# design.net
KiCad netlist of a schematic drawn in Altium Designer
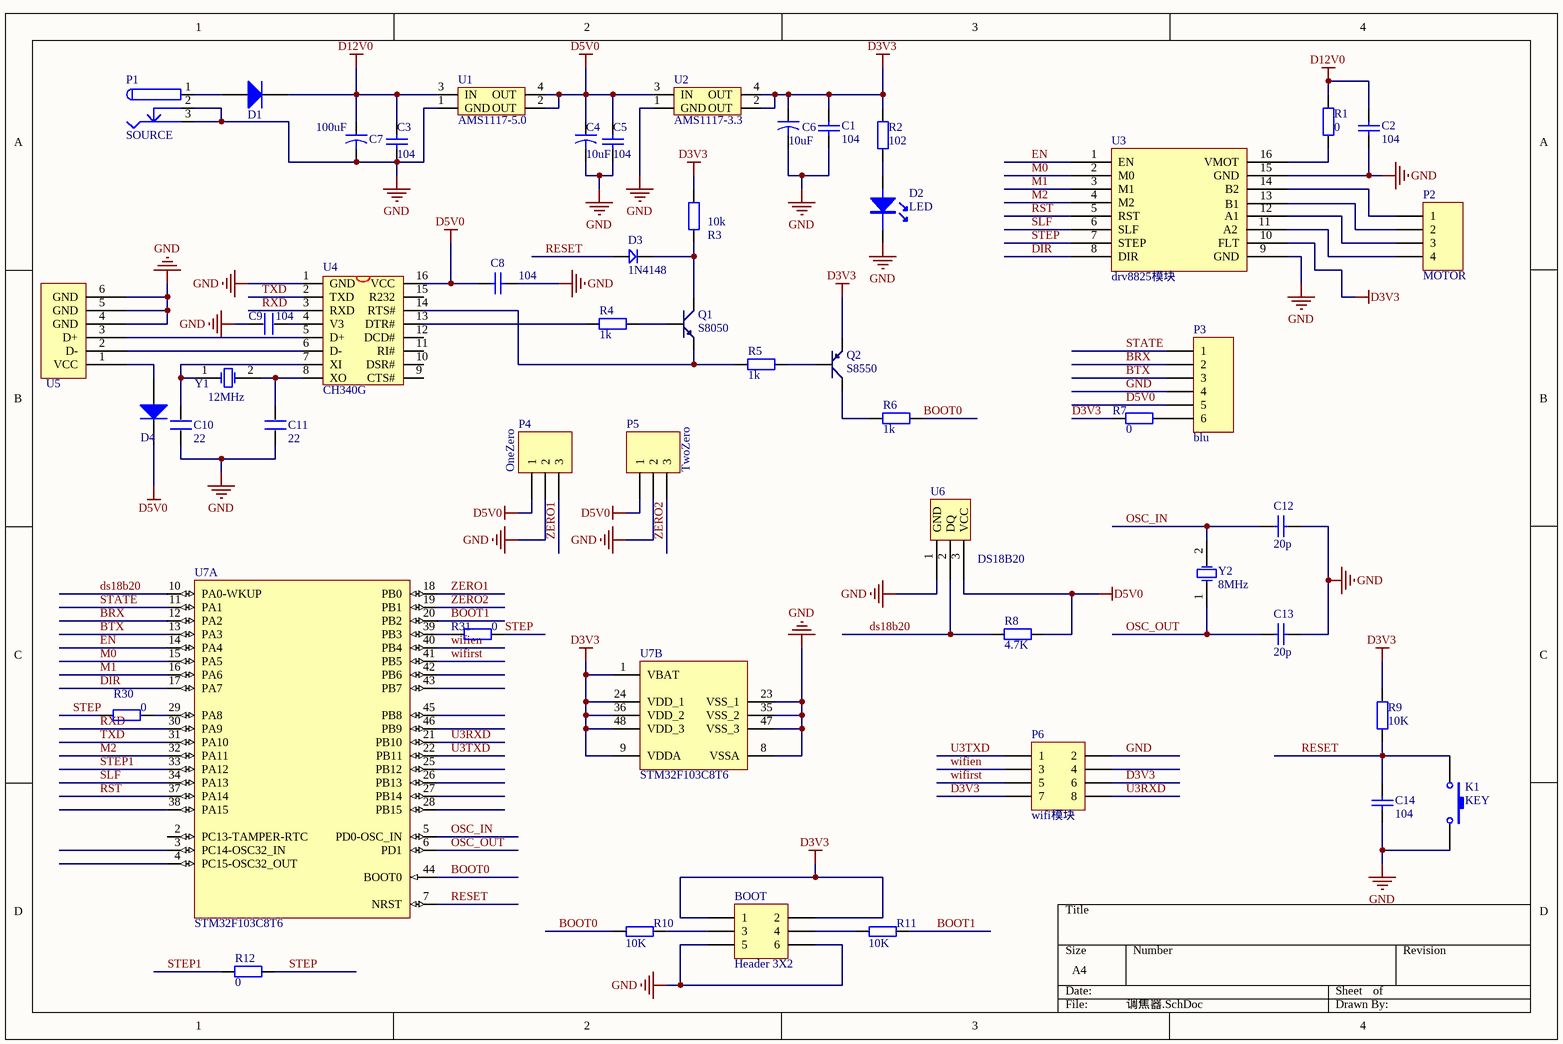
[diagram p0: 调焦器.SchDoc]

(export (version "E")
  (design (tool "Eeschema 10.0.6"))
  (components
    (comp (ref "BOOT")
      (value "Header 3X2")
      (footprint "HDR2X3")
      (description "Header, 3-Pin, Dual row")
      (fields (field (name "PUBLISHER") "Altium Limited"))
      (libsource (lib "WarShip V3 STM32103封装库") (part "Header 3X2"))
    )
    (comp (ref "C1")
      (value "104")
      (footprint "0805_cap")
      (description "Capacitor")
      (fields (field (name "Comment") "Cap") (field (name "PUBLISHER") "Altium Limited"))
      (libsource (lib "Crazy_PCB") (part "Cap"))
    )
    (comp (ref "C2")
      (value "104")
      (footprint "0805_cap")
      (description "Capacitor")
      (fields (field (name "Comment") "Cap") (field (name "PUBLISHER") "Altium Limited"))
      (libsource (lib "Crazy_PCB") (part "Cap"))
    )
    (comp (ref "C3")
      (value "104")
      (footprint "0805_cap")
      (description "Capacitor")
      (fields (field (name "Comment") "Cap") (field (name "PUBLISHER") "Altium Limited"))
      (libsource (lib "Crazy_PCB") (part "Cap"))
    )
    (comp (ref "C4")
      (value "CAP")
      (footprint "1812")
      (fields (field (name "VAULE") "10uF"))
      (libsource (lib "Crazy_PCB") (part "CAP2"))
    )
    (comp (ref "C5")
      (value "104")
      (footprint "0805_cap")
      (description "Capacitor")
      (fields (field (name "Comment") "Cap") (field (name "PUBLISHER") "Altium Limited"))
      (libsource (lib "Crazy_PCB") (part "Cap"))
    )
    (comp (ref "C6")
      (value "CAP")
      (footprint "1812")
      (fields (field (name "VAULE") "10uF"))
      (libsource (lib "Crazy_PCB") (part "CAP2"))
    )
    (comp (ref "C7")
      (value "CAP")
      (footprint "1000UF/16V")
      (fields (field (name "VAULE") "100uF"))
      (libsource (lib "Crazy_PCB") (part "CAP2"))
    )
    (comp (ref "C8")
      (value "104")
      (footprint "0805_cap")
      (description "Capacitor")
      (fields (field (name "Comment") "Cap") (field (name "PUBLISHER") "Altium Limited"))
      (libsource (lib "Crazy_PCB") (part "Cap"))
    )
    (comp (ref "C9") (value "104") (footprint "0805") (libsource (lib "WarShip V3 STM32103封装库") (part "C")))
    (comp (ref "C10") (value "22") (footprint "0805") (libsource (lib "WarShip V3 STM32103封装库") (part "C")))
    (comp (ref "C11") (value "22") (footprint "0805") (libsource (lib "WarShip V3 STM32103封装库") (part "C")))
    (comp (ref "C12")
      (value "20p")
      (footprint "0805_cap")
      (description "Capacitor")
      (fields (field (name "Comment") "Cap") (field (name "PUBLISHER") "Altium Limited"))
      (libsource (lib "Crazy_PCB") (part "Cap"))
    )
    (comp (ref "C13")
      (value "20p")
      (footprint "0805_cap")
      (description "Capacitor")
      (fields (field (name "Comment") "Cap") (field (name "PUBLISHER") "Altium Limited"))
      (libsource (lib "Crazy_PCB") (part "Cap"))
    )
    (comp (ref "C14")
      (value "104")
      (footprint "0805_cap")
      (description "Capacitor")
      (fields (field (name "Comment") "Cap") (field (name "PUBLISHER") "Altium Limited"))
      (libsource (lib "Crazy_PCB") (part "Cap"))
    )
    (comp (ref "D1")
      (value "Diode")
      (footprint "Diode")
      (description "High Conductance Fast Diode")
      (fields (field (name "PUBLISHER") "Altium Limited"))
      (libsource (lib "Crazy_PCB") (part "Diode"))
    )
    (comp (ref "D2")
      (value "LED")
      (footprint "LED")
      (description "LED 发光二极管")
      (libsource (lib "Crazy_PCB") (part "LED"))
    )
    (comp (ref "D3") (value "1N4148") (footprint "Diode") (libsource (lib "MiniSTM32 V3.0封装库") (part "D")))
    (comp (ref "D4")
      (value "Diode")
      (footprint "Diode")
      (description "High Conductance Fast Diode")
      (fields (field (name "PUBLISHER") "Altium Limited"))
      (libsource (lib "Crazy_PCB") (part "Diode"))
    )
    (comp (ref "K1")
      (value "KEY")
      (footprint "KEY2")
      (description "Switch")
      (fields (field (name "PUBLISHER") "Altium Limited"))
      (libsource (lib "Crazy_PCB") (part "KEY2"))
    )
    (comp (ref "P1")
      (value "SOURCE")
      (footprint "source")
      (fields (field (name "PUBLISHER") "Altium Limited"))
      (libsource (lib "Crazy_PCB") (part "SOURCE"))
    )
    (comp (ref "P2")
      (value "MOTOR")
      (footprint "HDR1X4")
      (description "Header, 4-Pin")
      (fields (field (name "PUBLISHER") "Altium Limited"))
      (libsource (lib "Miscellaneous Connectors") (part "Header 4"))
    )
    (comp (ref "P3")
      (value "blu")
      (footprint "HDR1X6")
      (description "Header, 6-Pin")
      (fields (field (name "PUBLISHER") "Altium Limited"))
      (libsource (lib "Miscellaneous Connectors") (part "Header 6"))
    )
    (comp (ref "P4")
      (value "OneZero")
      (footprint "HDR1X3")
      (description "Header, 3-Pin")
      (fields (field (name "PUBLISHER") "Altium Limited"))
      (libsource (lib "Miscellaneous Connectors") (part "Header 3"))
    )
    (comp (ref "P5")
      (value "TwoZero")
      (footprint "HDR1X3")
      (description "Header, 3-Pin")
      (fields (field (name "PUBLISHER") "Altium Limited"))
      (libsource (lib "Miscellaneous Connectors") (part "Header 3"))
    )
    (comp (ref "P6")
      (value "wifi模块")
      (footprint "HDR2X4")
      (description "Header, 4-Pin, Dual row")
      (fields (field (name "PUBLISHER") "Altium Limited"))
      (libsource (lib "Miscellaneous Connectors") (part "Header 4X2"))
    )
    (comp (ref "Q1")
      (value "S8050")
      (footprint "SOT-23R")
      (description "8050/BCW846/BCW847")
      (libsource (lib "MiniSTM32 V3.0封装库") (part "NPN"))
    )
    (comp (ref "Q2")
      (value "S8550")
      (footprint "SOT-23R")
      (description "8550/BCW68")
      (libsource (lib "MiniSTM32 V3.0封装库") (part "PNP"))
    )
    (comp (ref "R1")
      (value "0")
      (footprint "0805")
      (description "Resistor")
      (fields (field (name "PUBLISHER") "Altium Limited"))
      (libsource (lib "") (part "RES_1"))
    )
    (comp (ref "R2")
      (value "102")
      (footprint "0805")
      (description "Resistor")
      (fields (field (name "PUBLISHER") "Altium Limited"))
      (libsource (lib "") (part "RES_1"))
    )
    (comp (ref "R3")
      (value "10k")
      (footprint "0805")
      (description "Resistor")
      (fields (field (name "PUBLISHER") "Altium Limited"))
      (libsource (lib "") (part "RES_1"))
    )
    (comp (ref "R4")
      (value "1k")
      (footprint "0805")
      (description "Resistor")
      (fields (field (name "PUBLISHER") "Altium Limited"))
      (libsource (lib "Crazy_PCB") (part "RES"))
    )
    (comp (ref "R5")
      (value "1k")
      (footprint "0805")
      (description "Resistor")
      (fields (field (name "PUBLISHER") "Altium Limited"))
      (libsource (lib "Crazy_PCB") (part "RES"))
    )
    (comp (ref "R6")
      (value "1k")
      (footprint "0805")
      (description "Resistor")
      (fields (field (name "PUBLISHER") "Altium Limited"))
      (libsource (lib "Crazy_PCB") (part "RES"))
    )
    (comp (ref "R7")
      (value "0")
      (footprint "0805")
      (description "Resistor")
      (fields (field (name "PUBLISHER") "Altium Limited"))
      (libsource (lib "Crazy_PCB") (part "RES"))
    )
    (comp (ref "R8")
      (value "4.7K")
      (footprint "0805")
      (description "Resistor")
      (fields (field (name "PUBLISHER") "Altium Limited"))
      (libsource (lib "Crazy_PCB") (part "RES"))
    )
    (comp (ref "R9")
      (value "10K")
      (footprint "0805")
      (description "Resistor")
      (fields (field (name "PUBLISHER") "Altium Limited"))
      (libsource (lib "") (part "RES_1"))
    )
    (comp (ref "R10") (value "10K") (footprint "0805") (libsource (lib "WarShip V3 STM32103封装库") (part "R")))
    (comp (ref "R11") (value "10K") (footprint "0805") (libsource (lib "WarShip V3 STM32103封装库") (part "R")))
    (comp (ref "R12")
      (value "0")
      (footprint "0805")
      (description "Resistor")
      (fields (field (name "PUBLISHER") "Altium Limited"))
      (libsource (lib "Crazy_PCB") (part "RES"))
    )
    (comp (ref "R30")
      (value "0")
      (footprint "0805")
      (description "Resistor")
      (fields (field (name "PUBLISHER") "Altium Limited"))
      (libsource (lib "Crazy_PCB") (part "RES"))
    )
    (comp (ref "R31")
      (value "0")
      (footprint "0805")
      (description "Resistor")
      (fields (field (name "PUBLISHER") "Altium Limited"))
      (libsource (lib "Crazy_PCB") (part "RES"))
    )
    (comp (ref "U1")
      (value "AMS1117-5.0")
      (footprint "AMS1117")
      (libsource (lib "MiniSTM32 V3.0封装库") (part "AMS1117"))
    )
    (comp (ref "U2")
      (value "AMS1117-3.3")
      (footprint "AMS1117")
      (libsource (lib "MiniSTM32 V3.0封装库") (part "AMS1117"))
    )
    (comp (ref "U3")
      (value "drv8825模块")
      (footprint "DRV8825模块 - duplicate")
      (libsource (lib "DX") (part "drv8825模块"))
    )
    (comp (ref "U4")
      (value "CH340G")
      (footprint "SOP16M")
      (description "USB2UART")
      (libsource (lib "WarShip V3 STM32103封装库") (part "CH340G"))
    )
    (comp (ref "U5") (value "USB-B") (footprint "USB_B") (libsource (lib "DX") (part "USB-B")))
    (comp (ref "U6")
      (value "DS18B20")
      (footprint "DS18B20")
      (libsource (lib "MiniSTM32 V3.0封装库") (part "DS18B20"))
    )
    (comp (ref "U7")
      (value "STM32F103C8T6")
      (footprint "LQFP48_N")
      (libsource (lib "STMicroelectronics STM32 F1") (part "STM32F103C8T6"))
    )
    (comp (ref "Y1")
      (value "12MHz")
      (footprint "XTAL_US")
      (description "Crystal Oscillator")
      (fields (field (name "PUBLISHER") "Altium Limited"))
      (libsource (lib "WarShip V3 STM32103封装库") (part "XTAL"))
    )
    (comp (ref "Y2")
      (value "8MHz")
      (footprint "XTAL_US")
      (description "Crystal Oscillator")
      (fields (field (name "PUBLISHER") "Altium Limited"))
      (libsource (lib "MiniSTM32 V3.0封装库") (part "XTAL"))
    )
  )
  (nets
    (net (code "1") (name "/BOOT0") (class "Default")
      (node (ref "R10") (pin "1") (pintype "passive"))
      (node (ref "R6") (pin "2") (pinfunction "2_2") (pintype "passive"))
      (node (ref "U7") (pin "44") (pinfunction "BOOT0_44") (pintype "input"))
    )
    (net (code "2") (name "/BOOT1") (class "Default")
      (node (ref "R11") (pin "2") (pintype "passive"))
      (node (ref "U7") (pin "20") (pinfunction "PB2_20") (pintype "bidirectional"))
    )
    (net (code "3") (name "/BRX") (class "Default")
      (node (ref "P3") (pin "2") (pinfunction "2_2") (pintype "passive"))
      (node (ref "U7") (pin "12") (pinfunction "PA2_12") (pintype "bidirectional"))
    )
    (net (code "4") (name "/BTX") (class "Default")
      (node (ref "P3") (pin "3") (pinfunction "3_3") (pintype "passive"))
      (node (ref "U7") (pin "13") (pinfunction "PA3_13") (pintype "bidirectional"))
    )
    (net (code "5") (name "/DIR") (class "Default")
      (node (ref "U3") (pin "8") (pinfunction "DIR_8") (pintype "passive"))
      (node (ref "U7") (pin "17") (pinfunction "PA7_17") (pintype "bidirectional"))
    )
    (net (code "6") (name "/EN") (class "Default")
      (node (ref "U3") (pin "1") (pinfunction "EN_1") (pintype "passive"))
      (node (ref "U7") (pin "14") (pinfunction "PA4_14") (pintype "bidirectional"))
    )
    (net (code "7") (name "/M0") (class "Default")
      (node (ref "U3") (pin "2") (pinfunction "M0_2") (pintype "passive"))
      (node (ref "U7") (pin "15") (pinfunction "PA5_15") (pintype "bidirectional"))
    )
    (net (code "8") (name "/M1") (class "Default")
      (node (ref "U3") (pin "3") (pinfunction "M1_3") (pintype "passive"))
      (node (ref "U7") (pin "16") (pinfunction "PA6_16") (pintype "bidirectional"))
    )
    (net (code "9") (name "/M2") (class "Default")
      (node (ref "U3") (pin "4") (pinfunction "M2_4") (pintype "passive"))
      (node (ref "U7") (pin "32") (pinfunction "PA11_32") (pintype "bidirectional"))
    )
    (net (code "10") (name "/OSC_IN") (class "Default")
      (node (ref "C12") (pin "1") (pinfunction "1_1") (pintype "passive"))
      (node (ref "U7") (pin "5") (pinfunction "PD0-OSC_IN_5") (pintype "bidirectional"))
      (node (ref "Y2") (pin "2") (pinfunction "OSC2_2") (pintype "passive"))
    )
    (net (code "11") (name "/OSC_OUT") (class "Default")
      (node (ref "C13") (pin "1") (pinfunction "1_1") (pintype "passive"))
      (node (ref "U7") (pin "6") (pinfunction "PD1_6") (pintype "bidirectional"))
      (node (ref "Y2") (pin "1") (pinfunction "OSC1_1") (pintype "passive"))
    )
    (net (code "12") (name "/RESET") (class "Default")
      (node (ref "C14") (pin "2") (pinfunction "2_2") (pintype "passive"))
      (node (ref "D3") (pin "1") (pintype "passive"))
      (node (ref "K1") (pin "1") (pinfunction "1_1") (pintype "passive"))
      (node (ref "R9") (pin "1") (pinfunction "1_1") (pintype "passive"))
      (node (ref "U7") (pin "7") (pinfunction "NRST_7") (pintype "bidirectional"))
    )
    (net (code "13") (name "/RST") (class "Default")
      (node (ref "U3") (pin "5") (pinfunction "RST_5") (pintype "passive"))
      (node (ref "U7") (pin "37") (pinfunction "PA14_37") (pintype "bidirectional"))
    )
    (net (code "14") (name "/RXD") (class "Default")
      (node (ref "U4") (pin "3") (pinfunction "RXD_3") (pintype "passive"))
      (node (ref "U7") (pin "30") (pinfunction "PA9_30") (pintype "bidirectional"))
    )
    (net (code "15") (name "/SLF") (class "Default")
      (node (ref "U3") (pin "6") (pinfunction "SLF_6") (pintype "passive"))
      (node (ref "U7") (pin "34") (pinfunction "PA13_34") (pintype "bidirectional"))
    )
    (net (code "16") (name "/STATE") (class "Default")
      (node (ref "P3") (pin "1") (pinfunction "1_1") (pintype "passive"))
      (node (ref "U7") (pin "11") (pinfunction "PA1_11") (pintype "bidirectional"))
    )
    (net (code "17") (name "/STEP") (class "Default")
      (node (ref "R12") (pin "2") (pinfunction "2_2") (pintype "passive"))
      (node (ref "R30") (pin "1") (pinfunction "1_1") (pintype "passive"))
      (node (ref "R31") (pin "2") (pinfunction "2_2") (pintype "passive"))
      (node (ref "U3") (pin "7") (pinfunction "STEP_7") (pintype "passive"))
    )
    (net (code "18") (name "/STEP1") (class "Default")
      (node (ref "R12") (pin "1") (pinfunction "1_1") (pintype "passive"))
      (node (ref "U7") (pin "33") (pinfunction "PA12_33") (pintype "bidirectional"))
    )
    (net (code "19") (name "/TXD") (class "Default")
      (node (ref "U4") (pin "2") (pinfunction "TXD_2") (pintype "passive"))
      (node (ref "U7") (pin "31") (pinfunction "PA10_31") (pintype "bidirectional"))
    )
    (net (code "20") (name "/U3RXD") (class "Default")
      (node (ref "P6") (pin "8") (pinfunction "8_8") (pintype "passive"))
      (node (ref "U7") (pin "21") (pinfunction "PB10_21") (pintype "bidirectional"))
    )
    (net (code "21") (name "/U3TXD") (class "Default")
      (node (ref "P6") (pin "1") (pinfunction "1_1") (pintype "passive"))
      (node (ref "U7") (pin "22") (pinfunction "PB11_22") (pintype "bidirectional"))
    )
    (net (code "22") (name "/ZERO1") (class "Default")
      (node (ref "P4") (pin "3") (pinfunction "3_3") (pintype "passive"))
      (node (ref "U7") (pin "18") (pinfunction "PB0_18") (pintype "bidirectional"))
    )
    (net (code "23") (name "/ZERO2") (class "Default")
      (node (ref "P5") (pin "3") (pinfunction "3_3") (pintype "passive"))
      (node (ref "U7") (pin "19") (pinfunction "PB1_19") (pintype "bidirectional"))
    )
    (net (code "24") (name "/ds18b20") (class "Default")
      (node (ref "R8") (pin "1") (pinfunction "1_1") (pintype "passive"))
      (node (ref "U6") (pin "2") (pinfunction "DQ_2") (pintype "passive"))
      (node (ref "U7") (pin "10") (pinfunction "PA0-WKUP_10") (pintype "bidirectional"))
    )
    (net (code "25") (name "/wifien") (class "Default")
      (node (ref "P6") (pin "3") (pinfunction "3_3") (pintype "passive"))
      (node (ref "U7") (pin "40") (pinfunction "PB4_40") (pintype "bidirectional"))
    )
    (net (code "26") (name "/wifirst") (class "Default")
      (node (ref "P6") (pin "5") (pinfunction "5_5") (pintype "passive"))
      (node (ref "U7") (pin "41") (pinfunction "PB5_41") (pintype "bidirectional"))
    )
    (net (code "27") (name "D3V3") (class "Default")
      (node (ref "BOOT") (pin "1") (pinfunction "1_1") (pintype "passive"))
      (node (ref "BOOT") (pin "2") (pinfunction "2_2") (pintype "passive"))
      (node (ref "C1") (pin "2") (pinfunction "2_2") (pintype "passive"))
      (node (ref "C6") (pin "1") (pinfunction "1_1") (pintype "passive"))
      (node (ref "P6") (pin "6") (pinfunction "6_6") (pintype "passive"))
      (node (ref "P6") (pin "7") (pinfunction "7_7") (pintype "passive"))
      (node (ref "Q2") (pin "1") (pinfunction "E_1") (pintype "passive"))
      (node (ref "R2") (pin "2") (pinfunction "2_2") (pintype "passive"))
      (node (ref "R3") (pin "2") (pinfunction "2_2") (pintype "passive"))
      (node (ref "R7") (pin "1") (pinfunction "1_1") (pintype "passive"))
      (node (ref "R9") (pin "2") (pinfunction "2_2") (pintype "passive"))
      (node (ref "U2") (pin "2") (pinfunction "OUT_2") (pintype "passive"))
      (node (ref "U2") (pin "4") (pinfunction "OUT_4") (pintype "passive"))
      (node (ref "U3") (pin "10") (pinfunction "FLT_10") (pintype "passive"))
      (node (ref "U7") (pin "1") (pinfunction "VBAT_1") (pintype "power_in"))
      (node (ref "U7") (pin "24") (pinfunction "VDD_1_24") (pintype "power_in"))
      (node (ref "U7") (pin "36") (pinfunction "VDD_2_36") (pintype "power_in"))
      (node (ref "U7") (pin "48") (pinfunction "VDD_3_48") (pintype "power_in"))
      (node (ref "U7") (pin "9") (pinfunction "VDDA_9") (pintype "power_in"))
    )
    (net (code "28") (name "D5V0") (class "Default")
      (node (ref "C4") (pin "1") (pinfunction "1_1") (pintype "passive"))
      (node (ref "C5") (pin "2") (pinfunction "2_2") (pintype "passive"))
      (node (ref "C8") (pin "2") (pinfunction "2_2") (pintype "passive"))
      (node (ref "D4") (pin "2") (pinfunction "K_2") (pintype "passive"))
      (node (ref "P3") (pin "5") (pinfunction "5_5") (pintype "passive"))
      (node (ref "P4") (pin "1") (pinfunction "1_1") (pintype "passive"))
      (node (ref "P5") (pin "1") (pinfunction "1_1") (pintype "passive"))
      (node (ref "R8") (pin "2") (pinfunction "2_2") (pintype "passive"))
      (node (ref "U1") (pin "2") (pinfunction "OUT_2") (pintype "passive"))
      (node (ref "U1") (pin "4") (pinfunction "OUT_4") (pintype "passive"))
      (node (ref "U2") (pin "3") (pinfunction "IN_3") (pintype "passive"))
      (node (ref "U4") (pin "16") (pinfunction "VCC_16") (pintype "passive"))
      (node (ref "U6") (pin "3") (pinfunction "VCC_3") (pintype "passive"))
    )
    (net (code "29") (name "D12V0") (class "Default")
      (node (ref "C2") (pin "2") (pinfunction "2_2") (pintype "passive"))
      (node (ref "C3") (pin "2") (pinfunction "2_2") (pintype "passive"))
      (node (ref "C7") (pin "1") (pinfunction "1_1") (pintype "passive"))
      (node (ref "D1") (pin "2") (pinfunction "K_2") (pintype "passive"))
      (node (ref "R1") (pin "2") (pinfunction "2_2") (pintype "passive"))
      (node (ref "U1") (pin "3") (pinfunction "IN_3") (pintype "passive"))
    )
    (net (code "30") (name "GND") (class "Default")
      (node (ref "BOOT") (pin "5") (pinfunction "5_5") (pintype "passive"))
      (node (ref "BOOT") (pin "6") (pinfunction "6_6") (pintype "passive"))
      (node (ref "C1") (pin "1") (pinfunction "1_1") (pintype "passive"))
      (node (ref "C10") (pin "1") (pintype "passive"))
      (node (ref "C11") (pin "1") (pintype "passive"))
      (node (ref "C12") (pin "2") (pinfunction "2_2") (pintype "passive"))
      (node (ref "C13") (pin "2") (pinfunction "2_2") (pintype "passive"))
      (node (ref "C14") (pin "1") (pinfunction "1_1") (pintype "passive"))
      (node (ref "C2") (pin "1") (pinfunction "1_1") (pintype "passive"))
      (node (ref "C3") (pin "1") (pinfunction "1_1") (pintype "passive"))
      (node (ref "C4") (pin "2") (pinfunction "2_2") (pintype "passive"))
      (node (ref "C5") (pin "1") (pinfunction "1_1") (pintype "passive"))
      (node (ref "C6") (pin "2") (pinfunction "2_2") (pintype "passive"))
      (node (ref "C7") (pin "2") (pinfunction "2_2") (pintype "passive"))
      (node (ref "C8") (pin "1") (pinfunction "1_1") (pintype "passive"))
      (node (ref "C9") (pin "1") (pintype "passive"))
      (node (ref "D2") (pin "2") (pinfunction "K_2") (pintype "passive"))
      (node (ref "K1") (pin "2") (pinfunction "2_2") (pintype "passive"))
      (node (ref "P1") (pin "2") (pinfunction "2_2") (pintype "power_in"))
      (node (ref "P1") (pin "3") (pinfunction "3_3") (pintype "power_in"))
      (node (ref "P3") (pin "4") (pinfunction "4_4") (pintype "passive"))
      (node (ref "P4") (pin "2") (pinfunction "2_2") (pintype "passive"))
      (node (ref "P5") (pin "2") (pinfunction "2_2") (pintype "passive"))
      (node (ref "P6") (pin "2") (pinfunction "2_2") (pintype "passive"))
      (node (ref "U1") (pin "1") (pinfunction "GND_1") (pintype "passive"))
      (node (ref "U2") (pin "1") (pinfunction "GND_1") (pintype "passive"))
      (node (ref "U3") (pin "15") (pinfunction "GND_15") (pintype "passive"))
      (node (ref "U3") (pin "9") (pinfunction "GND_9") (pintype "passive"))
      (node (ref "U4") (pin "1") (pinfunction "GND_1") (pintype "passive"))
      (node (ref "U5") (pin "4") (pinfunction "GND_4") (pintype "passive"))
      (node (ref "U5") (pin "5") (pinfunction "GND_5") (pintype "passive"))
      (node (ref "U5") (pin "6") (pinfunction "GND_6") (pintype "passive"))
      (node (ref "U6") (pin "1") (pinfunction "GND_1") (pintype "passive"))
      (node (ref "U7") (pin "23") (pinfunction "VSS_1_23") (pintype "power_in"))
      (node (ref "U7") (pin "35") (pinfunction "VSS_2_35") (pintype "power_in"))
      (node (ref "U7") (pin "47") (pinfunction "VSS_3_47") (pintype "power_in"))
      (node (ref "U7") (pin "8") (pinfunction "VSSA_8") (pintype "power_in"))
    )
    (net (code "31") (name "Net-(BOOT-Pad3)") (class "Default")
      (node (ref "BOOT") (pin "3") (pinfunction "3_3") (pintype "passive"))
      (node (ref "R10") (pin "2") (pintype "passive"))
    )
    (net (code "32") (name "Net-(BOOT-Pad4)") (class "Default")
      (node (ref "BOOT") (pin "4") (pinfunction "4_4") (pintype "passive"))
      (node (ref "R11") (pin "1") (pintype "passive"))
    )
    (net (code "33") (name "Net-(D1-A)") (class "Default")
      (node (ref "D1") (pin "1") (pinfunction "A_1") (pintype "passive"))
      (node (ref "P1") (pin "1") (pinfunction "1_1") (pintype "power_in"))
    )
    (net (code "34") (name "Net-(D2-A)") (class "Default")
      (node (ref "D2") (pin "1") (pinfunction "A_1") (pintype "passive"))
      (node (ref "R2") (pin "1") (pinfunction "1_1") (pintype "passive"))
    )
    (net (code "35") (name "Net-(D4-A)") (class "Default")
      (node (ref "D4") (pin "1") (pinfunction "A_1") (pintype "passive"))
      (node (ref "U5") (pin "1") (pinfunction "VCC_1") (pintype "passive"))
    )
    (net (code "36") (name "Net-(P3-Pad6)") (class "Default")
      (node (ref "P3") (pin "6") (pinfunction "6_6") (pintype "passive"))
      (node (ref "R7") (pin "2") (pinfunction "2_2") (pintype "passive"))
    )
    (net (code "37") (name "Net-(Q1-B)") (class "Default")
      (node (ref "Q1") (pin "2") (pinfunction "B_2") (pintype "passive"))
      (node (ref "R4") (pin "2") (pinfunction "2_2") (pintype "passive"))
    )
    (net (code "38") (name "Net-(Q1-C)") (class "Default")
      (node (ref "D3") (pin "2") (pintype "passive"))
      (node (ref "Q1") (pin "3") (pinfunction "C_3") (pintype "passive"))
      (node (ref "R3") (pin "1") (pinfunction "1_1") (pintype "passive"))
    )
    (net (code "39") (name "Net-(Q1-E)") (class "Default")
      (node (ref "Q1") (pin "1") (pinfunction "E_1") (pintype "passive"))
      (node (ref "R5") (pin "1") (pinfunction "1_1") (pintype "passive"))
      (node (ref "U4") (pin "14") (pinfunction "RTS#_14") (pintype "passive"))
    )
    (net (code "40") (name "Net-(Q2-B)") (class "Default")
      (node (ref "Q2") (pin "2") (pinfunction "B_2") (pintype "passive"))
      (node (ref "R5") (pin "2") (pinfunction "2_2") (pintype "passive"))
    )
    (net (code "41") (name "Net-(Q2-C)") (class "Default")
      (node (ref "Q2") (pin "3") (pinfunction "C_3") (pintype "passive"))
      (node (ref "R6") (pin "1") (pinfunction "1_1") (pintype "passive"))
    )
    (net (code "42") (name "Net-(U3-A1)") (class "Default")
      (node (ref "P2") (pin "3") (pinfunction "3_3") (pintype "passive"))
      (node (ref "U3") (pin "12") (pinfunction "A1_12") (pintype "passive"))
    )
    (net (code "43") (name "Net-(U3-A2)") (class "Default")
      (node (ref "P2") (pin "4") (pinfunction "4_4") (pintype "passive"))
      (node (ref "U3") (pin "11") (pinfunction "A2_11") (pintype "passive"))
    )
    (net (code "44") (name "Net-(U3-B1)") (class "Default")
      (node (ref "P2") (pin "2") (pinfunction "2_2") (pintype "passive"))
      (node (ref "U3") (pin "13") (pinfunction "B1_13") (pintype "passive"))
    )
    (net (code "45") (name "Net-(U3-B2)") (class "Default")
      (node (ref "P2") (pin "1") (pinfunction "1_1") (pintype "passive"))
      (node (ref "U3") (pin "14") (pinfunction "B2_14") (pintype "passive"))
    )
    (net (code "46") (name "Net-(U3-VMOT)") (class "Default")
      (node (ref "R1") (pin "1") (pinfunction "1_1") (pintype "passive"))
      (node (ref "U3") (pin "16") (pinfunction "VMOT_16") (pintype "passive"))
    )
    (net (code "47") (name "Net-(U4-D+)") (class "Default")
      (node (ref "U4") (pin "5") (pinfunction "D+_5") (pintype "passive"))
      (node (ref "U5") (pin "3") (pinfunction "D+_3") (pintype "passive"))
    )
    (net (code "48") (name "Net-(U4-D-)") (class "Default")
      (node (ref "U4") (pin "6") (pinfunction "D-_6") (pintype "passive"))
      (node (ref "U5") (pin "2") (pinfunction "D-_2") (pintype "passive"))
    )
    (net (code "49") (name "Net-(U4-DTR#)") (class "Default")
      (node (ref "R4") (pin "1") (pinfunction "1_1") (pintype "passive"))
      (node (ref "U4") (pin "13") (pinfunction "DTR#_13") (pintype "passive"))
    )
    (net (code "50") (name "Net-(U4-V3)") (class "Default")
      (node (ref "C9") (pin "2") (pintype "passive"))
      (node (ref "U4") (pin "4") (pinfunction "V3_4") (pintype "passive"))
    )
    (net (code "51") (name "Net-(U4-XI)") (class "Default")
      (node (ref "C10") (pin "2") (pintype "passive"))
      (node (ref "U4") (pin "7") (pinfunction "XI_7") (pintype "passive"))
      (node (ref "Y1") (pin "1") (pinfunction "OSC1_1") (pintype "passive"))
    )
    (net (code "52") (name "Net-(U4-XO)") (class "Default")
      (node (ref "C11") (pin "2") (pintype "passive"))
      (node (ref "U4") (pin "8") (pinfunction "XO_8") (pintype "passive"))
      (node (ref "Y1") (pin "2") (pinfunction "OSC2_2") (pintype "passive"))
    )
    (net (code "53") (name "Net-(U7A-PA8)") (class "Default")
      (node (ref "R30") (pin "2") (pinfunction "2_2") (pintype "passive"))
      (node (ref "U7") (pin "29") (pinfunction "PA8_29") (pintype "bidirectional"))
    )
    (net (code "54") (name "Net-(U7A-PB3)") (class "Default")
      (node (ref "R31") (pin "1") (pinfunction "1_1") (pintype "passive"))
      (node (ref "U7") (pin "39") (pinfunction "PB3_39") (pintype "bidirectional"))
    )
    (net (code "55") (name "unconnected-(P6-Pad4)") (class "Default")
      (node (ref "P6") (pin "4") (pinfunction "4_4") (pintype "passive"))
    )
    (net (code "56") (name "unconnected-(U4-CTS#-Pad9)") (class "Default")
      (node (ref "U4") (pin "9") (pinfunction "CTS#_9") (pintype "passive"))
    )
    (net (code "57") (name "unconnected-(U4-DCD#-Pad12)") (class "Default")
      (node (ref "U4") (pin "12") (pinfunction "DCD#_12") (pintype "passive"))
    )
    (net (code "58") (name "unconnected-(U4-DSR#-Pad10)") (class "Default")
      (node (ref "U4") (pin "10") (pinfunction "DSR#_10") (pintype "passive"))
    )
    (net (code "59") (name "unconnected-(U4-R232-Pad15)") (class "Default")
      (node (ref "U4") (pin "15") (pinfunction "R232_15") (pintype "passive"))
    )
    (net (code "60") (name "unconnected-(U4-RI#-Pad11)") (class "Default")
      (node (ref "U4") (pin "11") (pinfunction "RI#_11") (pintype "passive"))
    )
    (net (code "61") (name "unconnected-(U7A-PA15-Pad38)") (class "Default")
      (node (ref "U7") (pin "38") (pinfunction "PA15_38") (pintype "bidirectional"))
    )
    (net (code "62") (name "unconnected-(U7A-PB6-Pad42)") (class "Default")
      (node (ref "U7") (pin "42") (pinfunction "PB6_42") (pintype "bidirectional"))
    )
    (net (code "63") (name "unconnected-(U7A-PB7-Pad43)") (class "Default")
      (node (ref "U7") (pin "43") (pinfunction "PB7_43") (pintype "bidirectional"))
    )
    (net (code "64") (name "unconnected-(U7A-PB8-Pad45)") (class "Default")
      (node (ref "U7") (pin "45") (pinfunction "PB8_45") (pintype "bidirectional"))
    )
    (net (code "65") (name "unconnected-(U7A-PB9-Pad46)") (class "Default")
      (node (ref "U7") (pin "46") (pinfunction "PB9_46") (pintype "bidirectional"))
    )
    (net (code "66") (name "unconnected-(U7A-PB12-Pad25)") (class "Default")
      (node (ref "U7") (pin "25") (pinfunction "PB12_25") (pintype "bidirectional"))
    )
    (net (code "67") (name "unconnected-(U7A-PB13-Pad26)") (class "Default")
      (node (ref "U7") (pin "26") (pinfunction "PB13_26") (pintype "bidirectional"))
    )
    (net (code "68") (name "unconnected-(U7A-PB14-Pad27)") (class "Default")
      (node (ref "U7") (pin "27") (pinfunction "PB14_27") (pintype "bidirectional"))
    )
    (net (code "69") (name "unconnected-(U7A-PB15-Pad28)") (class "Default")
      (node (ref "U7") (pin "28") (pinfunction "PB15_28") (pintype "bidirectional"))
    )
    (net (code "70") (name "unconnected-(U7A-PC13-TAMPER-RTC-Pad2)") (class "Default")
      (node (ref "U7") (pin "2") (pinfunction "PC13-TAMPER-RTC_2") (pintype "bidirectional"))
    )
    (net (code "71") (name "unconnected-(U7A-PC14-OSC32_IN-Pad3)") (class "Default")
      (node (ref "U7") (pin "3") (pinfunction "PC14-OSC32_IN_3") (pintype "bidirectional"))
    )
    (net (code "72") (name "unconnected-(U7A-PC15-OSC32_OUT-Pad4)") (class "Default")
      (node (ref "U7") (pin "4") (pinfunction "PC15-OSC32_OUT_4") (pintype "bidirectional"))
    )
  )
)
